# Gagabiro_mechanical.net
KiCad netlist of a schematic drawn in Altium Designer
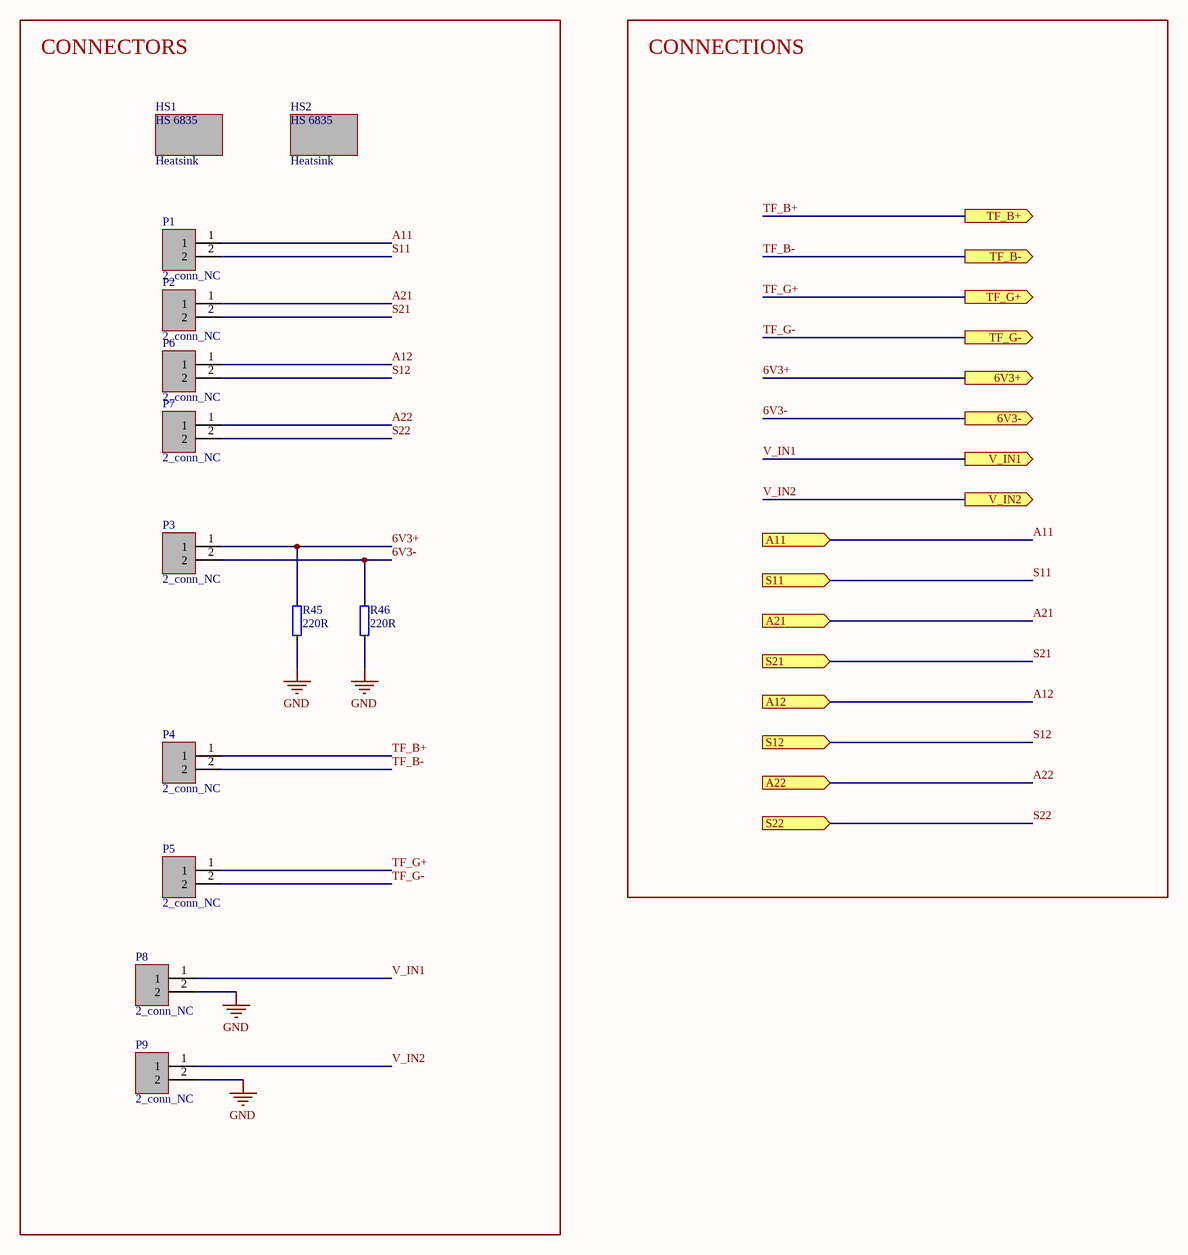
[diagram p0: Gagabiro_mechanical.SchDoc]

(export (version "E")
  (design (tool "Eeschema 10.0.6"))
  (components
    (comp (ref "HS1")
      (value "Heatsink")
      (footprint "heatsink_HS_6835")
      (libsource (lib "Gagabiro_Integrated_Library") (part "HS 6835"))
    )
    (comp (ref "HS2")
      (value "Heatsink")
      (footprint "heatsink_HS_6835")
      (libsource (lib "Gagabiro_Integrated_Library") (part "HS 6835"))
    )
    (comp (ref "P1")
      (value "2_conn_NC")
      (footprint "2_conn_NC")
      (description "Connector Header Surface Mount, Right Angle 2 position 0.079 (2.00mm)")
      (fields (field (name "MP") "S2B-PH-SM4-TB") (field (name "MF") "JST Sales"))
      (libsource (lib "Gagabiro_Integrated_Library") (part "2_conn_NC"))
    )
    (comp (ref "P2")
      (value "2_conn_NC")
      (footprint "2_conn_NC")
      (description "Connector Header Surface Mount, Right Angle 2 position 0.079 (2.00mm)")
      (fields (field (name "MP") "S2B-PH-SM4-TB") (field (name "MF") "JST Sales"))
      (libsource (lib "Gagabiro_Integrated_Library") (part "2_conn_NC"))
    )
    (comp (ref "P3")
      (value "2_conn_NC")
      (footprint "2_conn_NC")
      (description "Connector Header Surface Mount, Right Angle 2 position 0.079 (2.00mm)")
      (fields (field (name "MP") "S2B-PH-SM4-TB") (field (name "MF") "JST Sales"))
      (libsource (lib "Gagabiro_Integrated_Library") (part "2_conn_NC"))
    )
    (comp (ref "P4")
      (value "2_conn_NC")
      (footprint "2_conn_NC")
      (description "Connector Header Surface Mount, Right Angle 2 position 0.079 (2.00mm)")
      (fields (field (name "MP") "S2B-PH-SM4-TB") (field (name "MF") "JST Sales"))
      (libsource (lib "Gagabiro_Integrated_Library") (part "2_conn_NC"))
    )
    (comp (ref "P5")
      (value "2_conn_NC")
      (footprint "2_conn_NC")
      (description "Connector Header Surface Mount, Right Angle 2 position 0.079 (2.00mm)")
      (fields (field (name "MP") "S2B-PH-SM4-TB") (field (name "MF") "JST Sales"))
      (libsource (lib "Gagabiro_Integrated_Library") (part "2_conn_NC"))
    )
    (comp (ref "P6")
      (value "2_conn_NC")
      (footprint "2_conn_NC")
      (description "Connector Header Surface Mount, Right Angle 2 position 0.079 (2.00mm)")
      (fields (field (name "MP") "S2B-PH-SM4-TB") (field (name "MF") "JST Sales"))
      (libsource (lib "Gagabiro_Integrated_Library") (part "2_conn_NC"))
    )
    (comp (ref "P7")
      (value "2_conn_NC")
      (footprint "2_conn_NC")
      (description "Connector Header Surface Mount, Right Angle 2 position 0.079 (2.00mm)")
      (fields (field (name "MP") "S2B-PH-SM4-TB") (field (name "MF") "JST Sales"))
      (libsource (lib "Gagabiro_Integrated_Library") (part "2_conn_NC"))
    )
    (comp (ref "P8")
      (value "2_conn_NC")
      (footprint "2_conn_NC")
      (description "Connector Header Surface Mount, Right Angle 2 position 0.079 (2.00mm)")
      (fields (field (name "MP") "S2B-PH-SM4-TB") (field (name "MF") "JST Sales"))
      (libsource (lib "Gagabiro_Integrated_Library") (part "2_conn_NC"))
    )
    (comp (ref "P9")
      (value "2_conn_NC")
      (footprint "2_conn_NC")
      (description "Connector Header Surface Mount, Right Angle 2 position 0.079 (2.00mm)")
      (fields (field (name "MP") "S2B-PH-SM4-TB") (field (name "MF") "JST Sales"))
      (libsource (lib "Gagabiro_Integrated_Library") (part "2_conn_NC"))
    )
    (comp (ref "R45")
      (value "220R")
      (footprint "RES_2W_vertical")
      (description "Resistor, 2W")
      (fields (field (name "PART NUMBER") "R2W") (field (name "AUTHOR") "colombari"))
      (libsource (lib "Persephone_Integrated_Library") (part "R_2W_vertical_220R"))
    )
    (comp (ref "R46")
      (value "220R")
      (footprint "RES_2W_vertical")
      (description "Resistor, 2W")
      (fields (field (name "PART NUMBER") "R2W") (field (name "AUTHOR") "colombari"))
      (libsource (lib "Persephone_Integrated_Library") (part "R_2W_vertical_220R"))
    )
  )
  (nets
    (net (code "1") (name "/6V3+") (class "Default")
      (node (ref "P3") (pin "1") (pinfunction "1_1") (pintype "passive"))
      (node (ref "R45") (pin "2") (pinfunction "2_2") (pintype "passive"))
    )
    (net (code "2") (name "/6V3-") (class "Default")
      (node (ref "P3") (pin "2") (pinfunction "2_2") (pintype "passive"))
      (node (ref "R46") (pin "2") (pinfunction "2_2") (pintype "passive"))
    )
    (net (code "3") (name "/A11") (class "Default")
      (node (ref "P1") (pin "1") (pinfunction "1_1") (pintype "passive"))
    )
    (net (code "4") (name "/A12") (class "Default")
      (node (ref "P6") (pin "1") (pinfunction "1_1") (pintype "passive"))
    )
    (net (code "5") (name "/A21") (class "Default")
      (node (ref "P2") (pin "1") (pinfunction "1_1") (pintype "passive"))
    )
    (net (code "6") (name "/A22") (class "Default")
      (node (ref "P7") (pin "1") (pinfunction "1_1") (pintype "passive"))
    )
    (net (code "7") (name "/S11") (class "Default")
      (node (ref "P1") (pin "2") (pinfunction "2_2") (pintype "passive"))
    )
    (net (code "8") (name "/S12") (class "Default")
      (node (ref "P6") (pin "2") (pinfunction "2_2") (pintype "passive"))
    )
    (net (code "9") (name "/S21") (class "Default")
      (node (ref "P2") (pin "2") (pinfunction "2_2") (pintype "passive"))
    )
    (net (code "10") (name "/S22") (class "Default")
      (node (ref "P7") (pin "2") (pinfunction "2_2") (pintype "passive"))
    )
    (net (code "11") (name "/TF_B+") (class "Default")
      (node (ref "P4") (pin "1") (pinfunction "1_1") (pintype "passive"))
    )
    (net (code "12") (name "/TF_B-") (class "Default")
      (node (ref "P4") (pin "2") (pinfunction "2_2") (pintype "passive"))
    )
    (net (code "13") (name "/TF_G+") (class "Default")
      (node (ref "P5") (pin "1") (pinfunction "1_1") (pintype "passive"))
    )
    (net (code "14") (name "/TF_G-") (class "Default")
      (node (ref "P5") (pin "2") (pinfunction "2_2") (pintype "passive"))
    )
    (net (code "15") (name "/V_IN1") (class "Default")
      (node (ref "P8") (pin "1") (pinfunction "1_1") (pintype "passive"))
    )
    (net (code "16") (name "/V_IN2") (class "Default")
      (node (ref "P9") (pin "1") (pinfunction "1_1") (pintype "passive"))
    )
    (net (code "17") (name "GND") (class "Default")
      (node (ref "P8") (pin "2") (pinfunction "2_2") (pintype "passive"))
      (node (ref "P9") (pin "2") (pinfunction "2_2") (pintype "passive"))
      (node (ref "R45") (pin "1") (pinfunction "1_1") (pintype "passive"))
      (node (ref "R46") (pin "1") (pinfunction "1_1") (pintype "passive"))
    )
  )
)
